# 02-RTC.net
KiCad netlist of a schematic drawn in Altium Designer
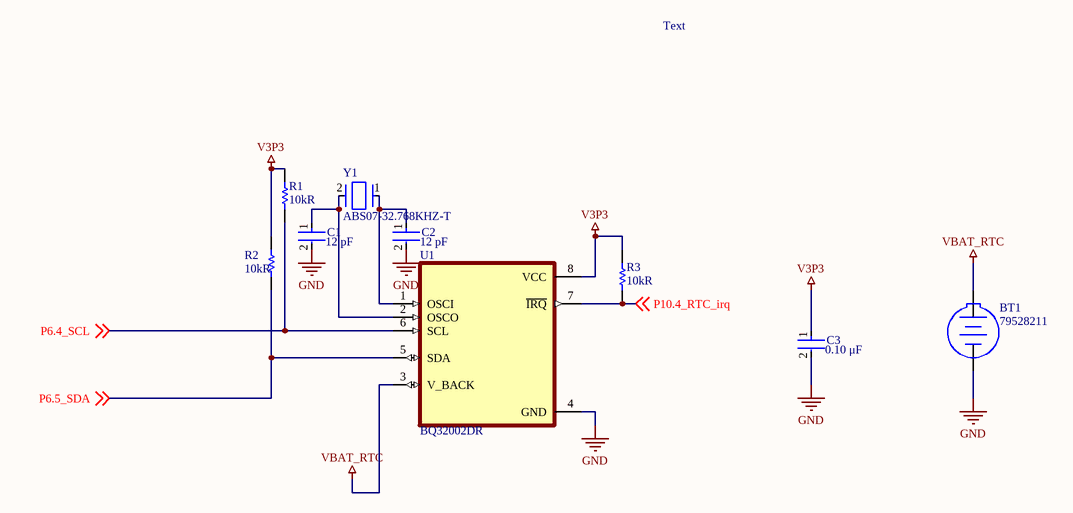
[diagram p0: 02-RTC.SchDoc]

(export (version "E")
  (design (tool "Eeschema 10.0.6"))
  (components
    (comp (ref "BT1")
      (value "79528211")
      (footprint "79528211")
      (description "79528211 Battery holder, 12VDC, 30 mOhm, 2025, 2032 battery type, black, THT mount")
      (libsource (lib "Altium Content Vault") (part "Battery Holder"))
    )
    (comp (ref "C1")
      (value "C0805C104K5RACTU")
      (footprint "FP-C0805C-DN-MFG")
      (description "CAP CER 0.1UF 50V X7R 0805")
      (fields
        (field (name "MANUFACTURER") "KEMET")
        (field (name "OCTOPART") "https://octopart.com/c0805c104k5ractu-kemet-143926")
        (field (name "CAPACITANCE") "12 pF")
      )
      (libsource (lib "Altium Content Vault") (part "b4654b650e69147ec39a6b967a45e02"))
    )
    (comp (ref "C2")
      (value "C0805C104K5RACTU")
      (footprint "FP-C0805C-DN-MFG")
      (description "CAP CER 0.1UF 50V X7R 0805")
      (fields
        (field (name "MANUFACTURER") "KEMET")
        (field (name "OCTOPART") "https://octopart.com/c0805c104k5ractu-kemet-143926")
        (field (name "CAPACITANCE") "12 pF")
      )
      (libsource (lib "Altium Content Vault") (part "b4654b650e69147ec39a6b967a45e02"))
    )
    (comp (ref "C3")
      (value "C0805C104K5RACTU")
      (footprint "FP-C0805C-DN-MFG")
      (description "CAP CER 0.1UF 50V X7R 0805")
      (fields
        (field (name "MANUFACTURER") "KEMET")
        (field (name "OCTOPART") "https://octopart.com/c0805c104k5ractu-kemet-143926")
        (field (name "CAPACITANCE") "0.10 μF")
      )
      (libsource (lib "Altium Content Vault") (part "b4654b650e69147ec39a6b967a45e02"))
    )
    (comp (ref "R1")
      (value "RC0805FR-0710KL")
      (footprint "RESC2013X60X35NL10T20")
      (description "Chip Resistor, 10 KOhm, +/- 1%, 0.125 W, -55 to 155 degC, 0805 (2012 Metric), RoHS, Tape and Reel")
      (fields
        (field (name "MANUFACTURER") "Yageo")
        (field (name "RESISTANCE") "10kR")
        (field (name "TOLERANCE") "1%")
      )
      (libsource (lib "Altium Content Vault") (part "RES-2"))
    )
    (comp (ref "R2")
      (value "RC0805FR-0710KL")
      (footprint "RESC2013X60X35NL10T20")
      (description "Chip Resistor, 10 KOhm, +/- 1%, 0.125 W, -55 to 155 degC, 0805 (2012 Metric), RoHS, Tape and Reel")
      (fields
        (field (name "MANUFACTURER") "Yageo")
        (field (name "RESISTANCE") "10kR")
        (field (name "TOLERANCE") "1%")
      )
      (libsource (lib "Altium Content Vault") (part "RES-2"))
    )
    (comp (ref "R3")
      (value "RC0805FR-0710KL")
      (footprint "RESC2013X60X35NL10T20")
      (description "Chip Resistor, 10 KOhm, +/- 1%, 0.125 W, -55 to 155 degC, 0805 (2012 Metric), RoHS, Tape and Reel")
      (fields
        (field (name "MANUFACTURER") "Yageo")
        (field (name "RESISTANCE") "10kR")
        (field (name "TOLERANCE") "1%")
      )
      (libsource (lib "Altium Content Vault") (part "RES-2"))
    )
    (comp (ref "U1")
      (value "BQ32002DR")
      (footprint "SOIC127P599X175-8N")
      (description "Real-time clock (RTC) with automatic switchover to backup supply")
      (fields (field (name "MF") "Texas Instruments"))
      (libsource (lib "my_parts") (part "BQ32002DR"))
    )
    (comp (ref "Y1")
      (value "ABS07-32.768KHZ-T")
      (footprint "FP-ABS07-MFG")
      (description "Crystal 32.768kHz ±20ppm (Tol) 12.5pF FUND 70kΩ 2-Pin CSMD T/R")
      (fields (field (name "TOLERANCE") "20ppm"))
      (libsource (lib "Altium Content Vault") (part "c23a69dc6c9e2f18f2079038eb95dd1"))
    )
  )
  (nets
    (net (code "1") (name "GND") (class "Default")
      (node (ref "BT1") (pin "2") (pinfunction "-_2") (pintype "passive"))
      (node (ref "C1") (pin "2") (pinfunction "2_2") (pintype "passive"))
      (node (ref "C2") (pin "2") (pinfunction "2_2") (pintype "passive"))
      (node (ref "C3") (pin "2") (pinfunction "2_2") (pintype "passive"))
      (node (ref "U1") (pin "4") (pinfunction "GND_4") (pintype "power_in"))
    )
    (net (code "2") (name "Net-(U1-OSCI)") (class "Default")
      (node (ref "C2") (pin "1") (pinfunction "1_1") (pintype "passive"))
      (node (ref "U1") (pin "1") (pinfunction "OSCI_1") (pintype "input"))
      (node (ref "Y1") (pin "1") (pinfunction "1_1") (pintype "passive"))
    )
    (net (code "3") (name "Net-(U1-OSCO)") (class "Default")
      (node (ref "C1") (pin "1") (pinfunction "1_1") (pintype "passive"))
      (node (ref "U1") (pin "2") (pinfunction "OSCO_2") (pintype "input"))
      (node (ref "Y1") (pin "2") (pinfunction "2_2") (pintype "passive"))
    )
    (net (code "4") (name "P6.4_SCL") (class "Default")
      (node (ref "R1") (pin "2") (pinfunction "2_2") (pintype "passive"))
      (node (ref "U1") (pin "6") (pinfunction "SCL_6") (pintype "input"))
    )
    (net (code "5") (name "P6.5_SDA") (class "Default")
      (node (ref "R2") (pin "2") (pinfunction "2_2") (pintype "passive"))
      (node (ref "U1") (pin "5") (pinfunction "SDA_5") (pintype "bidirectional"))
    )
    (net (code "6") (name "P10.4_RTC_irq") (class "Default")
      (node (ref "R3") (pin "2") (pinfunction "2_2") (pintype "passive"))
      (node (ref "U1") (pin "7") (pinfunction "~{IRQ}_7") (pintype "output"))
    )
    (net (code "7") (name "V3P3") (class "Default")
      (node (ref "C3") (pin "1") (pinfunction "1_1") (pintype "passive"))
      (node (ref "R1") (pin "1") (pinfunction "1_1") (pintype "passive"))
      (node (ref "R2") (pin "1") (pinfunction "1_1") (pintype "passive"))
      (node (ref "R3") (pin "1") (pinfunction "1_1") (pintype "passive"))
      (node (ref "U1") (pin "8") (pinfunction "VCC_8") (pintype "power_in"))
    )
    (net (code "8") (name "VBAT_RTC") (class "Default")
      (node (ref "BT1") (pin "1") (pinfunction "+_1") (pintype "passive"))
      (node (ref "U1") (pin "3") (pinfunction "V_BACK_3") (pintype "bidirectional"))
    )
  )
)
